# BaseNode.net
KiCad netlist of a schematic drawn in Altium Designer
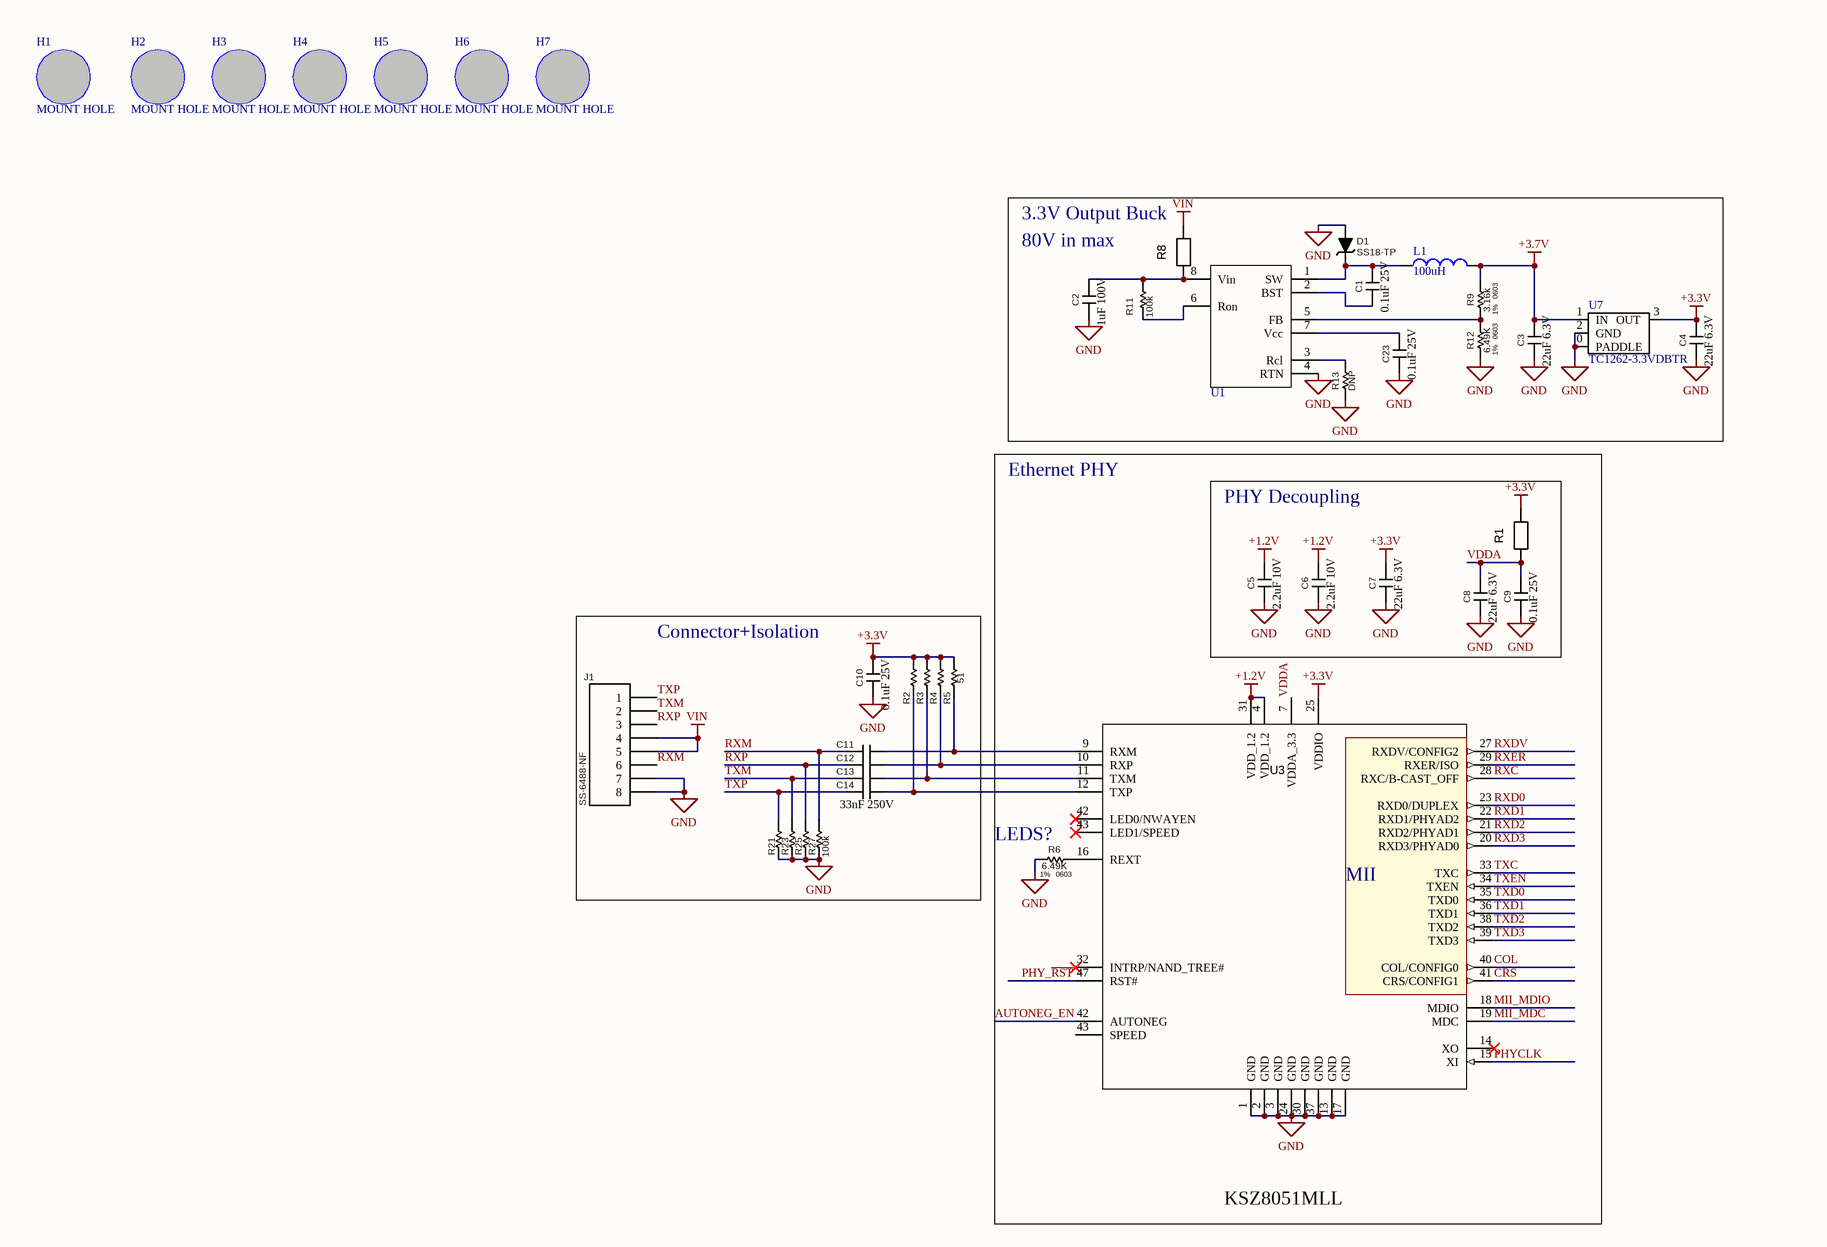
[diagram p0: BaseNode.SchDoc, top left]
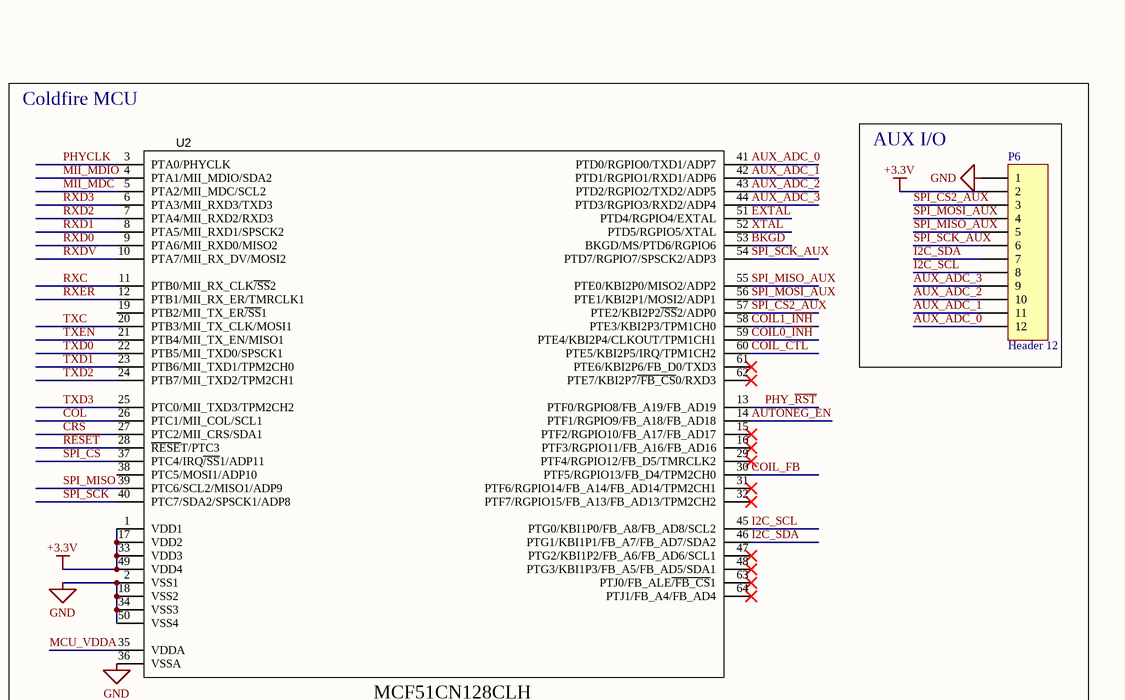
[diagram p1: BaseNode.SchDoc, top right]
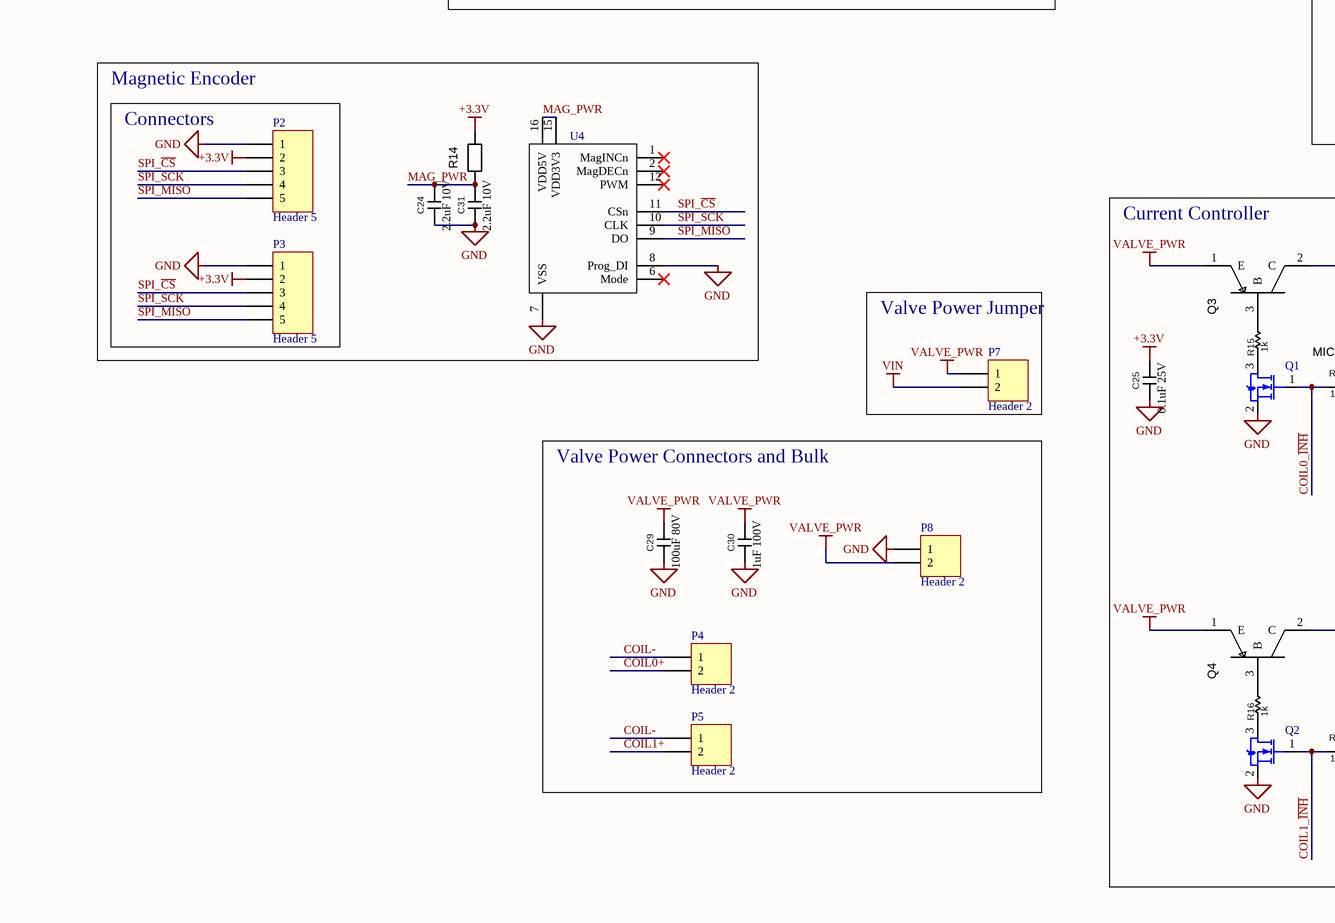
[diagram p2: BaseNode.SchDoc, bottom left]
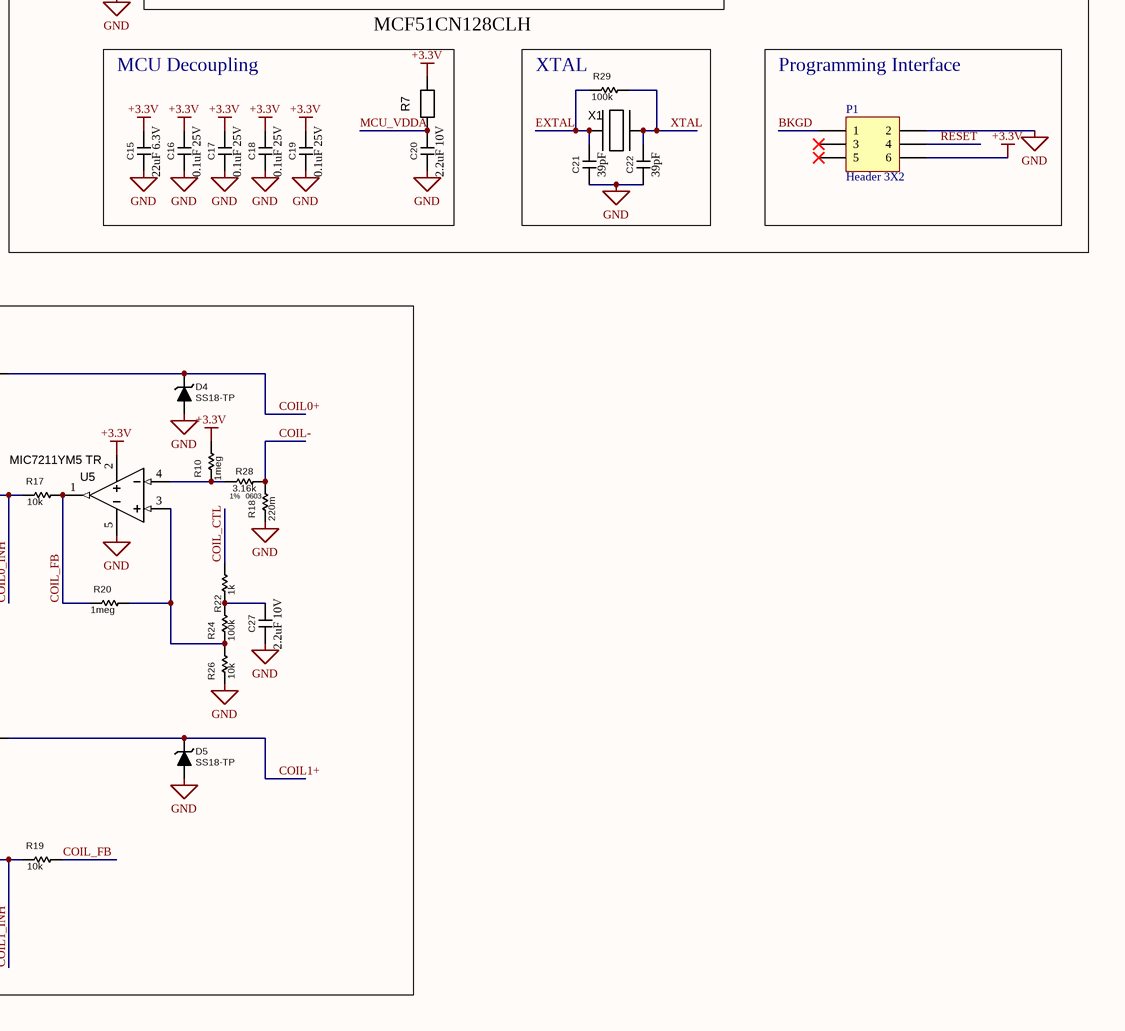
[diagram p3: BaseNode.SchDoc, bottom right]

(export (version "E")
  (design (tool "Eeschema 10.0.6"))
  (components
    (comp (ref "C1")
      (value "0.1uF 25V")
      (footprint "whong:0603")
      (description "Capacitor")
      (fields (field (name "MANUFACTURER") "Murata Electronics North America"))
      (libsource (lib "whong") (part "Capacitor"))
    )
    (comp (ref "C2")
      (value "1uF 100V")
      (footprint "whong:0805")
      (description "Capacitor")
      (fields (field (name "MANUFACTURER") "TDK Corporation"))
      (libsource (lib "whong") (part "Capacitor"))
    )
    (comp (ref "C3")
      (value "22uF 6.3V")
      (footprint "whong:1206")
      (description "Capacitor")
      (fields (field (name "MANUFACTURER") "Taiyo Yuden"))
      (libsource (lib "whong") (part "Capacitor"))
    )
    (comp (ref "C4")
      (value "22uF 6.3V")
      (footprint "whong:1206")
      (description "Capacitor")
      (fields (field (name "MANUFACTURER") "Taiyo Yuden"))
      (libsource (lib "whong") (part "Capacitor"))
    )
    (comp (ref "C5")
      (value "2.2uF 10V")
      (footprint "whong:0603")
      (description "Capacitor")
      (fields (field (name "MANUFACTURER") "Taiyo Yuden"))
      (libsource (lib "whong") (part "Capacitor"))
    )
    (comp (ref "C6")
      (value "2.2uF 10V")
      (footprint "whong:0603")
      (description "Capacitor")
      (fields (field (name "MANUFACTURER") "Taiyo Yuden"))
      (libsource (lib "whong") (part "Capacitor"))
    )
    (comp (ref "C7")
      (value "22uF 6.3V")
      (footprint "whong:1206")
      (description "Capacitor")
      (fields (field (name "MANUFACTURER") "Taiyo Yuden"))
      (libsource (lib "whong") (part "Capacitor"))
    )
    (comp (ref "C8")
      (value "22uF 6.3V")
      (footprint "whong:1206")
      (description "Capacitor")
      (fields (field (name "MANUFACTURER") "Taiyo Yuden"))
      (libsource (lib "whong") (part "Capacitor"))
    )
    (comp (ref "C9")
      (value "0.1uF 25V")
      (footprint "whong:0603")
      (description "Capacitor")
      (fields (field (name "MANUFACTURER") "Murata Electronics North America"))
      (libsource (lib "whong") (part "Capacitor"))
    )
    (comp (ref "C10")
      (value "0.1uF 25V")
      (footprint "whong:0603")
      (description "Capacitor")
      (fields (field (name "MANUFACTURER") "Murata Electronics North America"))
      (libsource (lib "whong") (part "Capacitor"))
    )
    (comp (ref "C11")
      (value "33nF 250V")
      (footprint "whong:0805")
      (description "Capacitor")
      (fields (field (name "MANUFACTURER") "TDK Corporation"))
      (libsource (lib "whong") (part "Capacitor"))
    )
    (comp (ref "C12")
      (value "33nF 250V")
      (footprint "whong:0805")
      (description "Capacitor")
      (fields (field (name "MANUFACTURER") "TDK Corporation"))
      (libsource (lib "whong") (part "Capacitor"))
    )
    (comp (ref "C13")
      (value "33nF 250V")
      (footprint "whong:0805")
      (description "Capacitor")
      (fields (field (name "MANUFACTURER") "TDK Corporation"))
      (libsource (lib "whong") (part "Capacitor"))
    )
    (comp (ref "C14")
      (value "33nF 250V")
      (footprint "whong:0805")
      (description "Capacitor")
      (fields (field (name "MANUFACTURER") "TDK Corporation"))
      (libsource (lib "whong") (part "Capacitor"))
    )
    (comp (ref "C15")
      (value "22uF 6.3V")
      (footprint "whong:1206")
      (description "Capacitor")
      (fields (field (name "MANUFACTURER") "Taiyo Yuden"))
      (libsource (lib "whong") (part "Capacitor"))
    )
    (comp (ref "C16")
      (value "0.1uF 25V")
      (footprint "whong:0603")
      (description "Capacitor")
      (fields (field (name "MANUFACTURER") "Murata Electronics North America"))
      (libsource (lib "whong") (part "Capacitor"))
    )
    (comp (ref "C17")
      (value "0.1uF 25V")
      (footprint "whong:0603")
      (description "Capacitor")
      (fields (field (name "MANUFACTURER") "Murata Electronics North America"))
      (libsource (lib "whong") (part "Capacitor"))
    )
    (comp (ref "C18")
      (value "0.1uF 25V")
      (footprint "whong:0603")
      (description "Capacitor")
      (fields (field (name "MANUFACTURER") "Murata Electronics North America"))
      (libsource (lib "whong") (part "Capacitor"))
    )
    (comp (ref "C19")
      (value "0.1uF 25V")
      (footprint "whong:0603")
      (description "Capacitor")
      (fields (field (name "MANUFACTURER") "Murata Electronics North America"))
      (libsource (lib "whong") (part "Capacitor"))
    )
    (comp (ref "C20")
      (value "2.2uF 10V")
      (footprint "whong:0603")
      (description "Capacitor")
      (fields (field (name "MANUFACTURER") "Taiyo Yuden"))
      (libsource (lib "whong") (part "Capacitor"))
    )
    (comp (ref "C21")
      (value "39pF")
      (footprint "whong:0603")
      (description "Capacitor")
      (fields (field (name "MANUFACTURER") "TDK Corporation"))
      (libsource (lib "whong") (part "Capacitor"))
    )
    (comp (ref "C22")
      (value "39pF")
      (footprint "whong:0603")
      (description "Capacitor")
      (fields (field (name "MANUFACTURER") "TDK Corporation"))
      (libsource (lib "whong") (part "Capacitor"))
    )
    (comp (ref "C23")
      (value "0.1uF 25V")
      (footprint "whong:0603")
      (description "Capacitor")
      (fields (field (name "MANUFACTURER") "Murata Electronics North America"))
      (libsource (lib "whong") (part "Capacitor"))
    )
    (comp (ref "C24")
      (value "2.2uF 10V")
      (footprint "whong:0603")
      (description "Capacitor")
      (fields (field (name "MANUFACTURER") "Taiyo Yuden"))
      (libsource (lib "whong") (part "Capacitor"))
    )
    (comp (ref "C25")
      (value "0.1uF 25V")
      (footprint "whong:0603")
      (description "Capacitor")
      (fields (field (name "MANUFACTURER") "Murata Electronics North America"))
      (libsource (lib "whong") (part "Capacitor"))
    )
    (comp (ref "C27")
      (value "2.2uF 10V")
      (footprint "whong:0603")
      (description "Capacitor")
      (fields (field (name "MANUFACTURER") "Taiyo Yuden"))
      (libsource (lib "whong") (part "Capacitor"))
    )
    (comp (ref "C29")
      (value "100uF 80V")
      (footprint "whong:Capacitor 12mm DIA POLAR")
      (description "Capacitor")
      (fields (field (name "MANUFACTURER") "Panasonic Electronic Components"))
      (libsource (lib "whong") (part "Capacitor"))
    )
    (comp (ref "C30")
      (value "1uF 100V")
      (footprint "whong:0805")
      (description "Capacitor")
      (fields (field (name "MANUFACTURER") "TDK Corporation"))
      (libsource (lib "whong") (part "Capacitor"))
    )
    (comp (ref "C31")
      (value "2.2uF 10V")
      (footprint "whong:0603")
      (description "Capacitor")
      (fields (field (name "MANUFACTURER") "Taiyo Yuden"))
      (libsource (lib "whong") (part "Capacitor"))
    )
    (comp (ref "D1")
      (value "CDBA140-G")
      (footprint "SMA-DIODE")
      (description "DIODE SCHOTTKY 40V 1A SMA")
      (fields (field (name "MANUFACTURER") "Micro Commercial Co") (field (name "MANUFACTURERPN") "SS18-TP"))
      (libsource (lib "whong") (part "CDBA140-G"))
    )
    (comp (ref "D4")
      (value "CDBA140-G")
      (footprint "SMA-DIODE")
      (description "DIODE SCHOTTKY 40V 1A SMA")
      (fields (field (name "MANUFACTURER") "Micro Commercial Co") (field (name "MANUFACTURERPN") "SS18-TP"))
      (libsource (lib "whong") (part "CDBA140-G"))
    )
    (comp (ref "D5")
      (value "CDBA140-G")
      (footprint "SMA-DIODE")
      (description "DIODE SCHOTTKY 40V 1A SMA")
      (fields (field (name "MANUFACTURER") "Micro Commercial Co") (field (name "MANUFACTURERPN") "SS18-TP"))
      (libsource (lib "whong") (part "CDBA140-G"))
    )
    (comp (ref "H1")
      (value "MOUNT HOLE")
      (footprint "MOUNT_HOLE")
      (libsource (lib "whong") (part "MOUNT HOLE"))
    )
    (comp (ref "H2")
      (value "MOUNT HOLE")
      (footprint "MOUNT_HOLE")
      (libsource (lib "whong") (part "MOUNT HOLE"))
    )
    (comp (ref "H3")
      (value "MOUNT HOLE")
      (footprint "MOUNT_HOLE")
      (libsource (lib "whong") (part "MOUNT HOLE"))
    )
    (comp (ref "H4")
      (value "MOUNT HOLE")
      (footprint "MOUNT_HOLE")
      (libsource (lib "whong") (part "MOUNT HOLE"))
    )
    (comp (ref "H5")
      (value "MOUNT HOLE")
      (footprint "MOUNT_HOLE")
      (libsource (lib "whong") (part "MOUNT HOLE"))
    )
    (comp (ref "H6")
      (value "MOUNT HOLE")
      (footprint "MOUNT_HOLE")
      (libsource (lib "whong") (part "MOUNT HOLE"))
    )
    (comp (ref "H7")
      (value "MOUNT HOLE")
      (footprint "MOUNT_HOLE")
      (libsource (lib "whong") (part "MOUNT HOLE"))
    )
    (comp (ref "J1")
      (value "SS-6488-NF")
      (footprint "whong:SS-6488-NF")
      (description "CONN 8-8 MOD JACK")
      (fields (field (name "MANUFACTURER") "Stewart Connector"))
      (libsource (lib "whong") (part "SS-6488-NF"))
    )
    (comp (ref "L1")
      (value "100uH")
      (footprint "whong:NR6028 Inductor")
      (description "Inductor")
      (fields (field (name "MANUFACTURER") "Taiyo Yuden"))
      (libsource (lib "Miscellaneous Devices") (part "Inductor"))
    )
    (comp (ref "P1")
      (value "Header 3X2")
      (footprint "HDR2X3")
      (description "Header, 3-Pin, Dual row")
      (fields (field (name "PUBLISHER") "Altium Limited"))
      (libsource (lib "Miscellaneous Connectors") (part "Header 3X2"))
    )
    (comp (ref "P2")
      (value "Header 5")
      (footprint "HDR1X5")
      (description "Header, 5-Pin")
      (fields (field (name "PUBLISHER") "Altium Limited"))
      (libsource (lib "Miscellaneous Connectors") (part "Header 5"))
    )
    (comp (ref "P3")
      (value "Header 5")
      (footprint "HDR1X5")
      (description "Header, 5-Pin")
      (fields (field (name "PUBLISHER") "Altium Limited"))
      (libsource (lib "Miscellaneous Connectors") (part "Header 5"))
    )
    (comp (ref "P4")
      (value "Header 2")
      (footprint "HDR1X2")
      (description "Header, 2-Pin")
      (fields (field (name "PUBLISHER") "Altium Limited"))
      (libsource (lib "Miscellaneous Connectors") (part "Header 2"))
    )
    (comp (ref "P5")
      (value "Header 2")
      (footprint "HDR1X2")
      (description "Header, 2-Pin")
      (fields (field (name "PUBLISHER") "Altium Limited"))
      (libsource (lib "Miscellaneous Connectors") (part "Header 2"))
    )
    (comp (ref "P6")
      (value "Header 12")
      (footprint "HDR1X12")
      (description "Header, 12-Pin")
      (fields (field (name "PUBLISHER") "Altium Limited"))
      (libsource (lib "Miscellaneous Connectors") (part "Header 12"))
    )
    (comp (ref "P7")
      (value "Header 2")
      (footprint "HDR1X2")
      (description "Header, 2-Pin")
      (fields (field (name "PUBLISHER") "Altium Limited"))
      (libsource (lib "Miscellaneous Connectors") (part "Header 2"))
    )
    (comp (ref "P8")
      (value "Header 2")
      (footprint "HDR1X2")
      (description "Header, 2-Pin")
      (fields (field (name "PUBLISHER") "Altium Limited"))
      (libsource (lib "Miscellaneous Connectors") (part "Header 2"))
    )
    (comp (ref "Q1")
      (value "NFET")
      (footprint "whong:SOT-23")
      (description "FET N-CH 100V 170MA SOT-23")
      (fields (field (name "MANUFACTURER") "Fairchild Semiconductor"))
      (libsource (lib "whong") (part "BSS123"))
    )
    (comp (ref "Q2")
      (value "NFET")
      (footprint "whong:SOT-23")
      (description "FET N-CH 100V 170MA SOT-23")
      (fields (field (name "MANUFACTURER") "Fairchild Semiconductor"))
      (libsource (lib "whong") (part "BSS123"))
    )
    (comp (ref "Q3")
      (value "~")
      (footprint "whong:SOT-89 - PBSS305PX")
      (description "TRANS PNP 80V 4A SOT89")
      (fields (field (name "MANUFACTURER") "NXP Semiconductors"))
      (libsource (lib "whong") (part "PBSS305PX,115"))
    )
    (comp (ref "Q4")
      (value "~")
      (footprint "whong:SOT-89 - PBSS305PX")
      (description "TRANS PNP 80V 4A SOT89")
      (fields (field (name "MANUFACTURER") "NXP Semiconductors"))
      (libsource (lib "whong") (part "PBSS305PX,115"))
    )
    (comp (ref "R1")
      (value "LM4041EIM3X-1.2_1")
      (footprint "whong:0603")
      (description "Ferrite")
      (fields (field (name "MANUFACTURER") "TDK Corporation"))
      (libsource (lib "whong") (part "LM4041EIM3X-1.2_1"))
    )
    (comp (ref "R2")
      (value "51")
      (footprint "whong:0603")
      (description "Resistor")
      (fields (field (name "MANUFACTURER") "Yageo") (field (name "TOLERANCE") "5%"))
      (libsource (lib "whong") (part "Resistor"))
    )
    (comp (ref "R3")
      (value "51")
      (footprint "whong:0603")
      (description "Resistor")
      (fields (field (name "MANUFACTURER") "Yageo") (field (name "TOLERANCE") "5%"))
      (libsource (lib "whong") (part "Resistor"))
    )
    (comp (ref "R4")
      (value "51")
      (footprint "whong:0603")
      (description "Resistor")
      (fields (field (name "MANUFACTURER") "Yageo") (field (name "TOLERANCE") "5%"))
      (libsource (lib "whong") (part "Resistor"))
    )
    (comp (ref "R5")
      (value "51")
      (footprint "whong:0603")
      (description "Resistor")
      (fields (field (name "MANUFACTURER") "Yageo") (field (name "TOLERANCE") "5%"))
      (libsource (lib "whong") (part "Resistor"))
    )
    (comp (ref "R6")
      (value "6.49K")
      (footprint "whong:0603")
      (description "Resistor")
      (fields
        (field (name "MANUFACTURER") "Yageo")
        (field (name "PACKAGE") "0603")
        (field (name "TOLERANCE") "1%")
      )
      (libsource (lib "JamesWhong") (part "Resistor"))
    )
    (comp (ref "R7")
      (value "LM4041EIM3X-1.2_1")
      (footprint "whong:0603")
      (description "Ferrite")
      (fields (field (name "MANUFACTURER") "TDK Corporation"))
      (libsource (lib "whong") (part "LM4041EIM3X-1.2_1"))
    )
    (comp (ref "R8")
      (value "LM4041EIM3X-1.2_1")
      (footprint "whong:0603")
      (description "Ferrite")
      (fields (field (name "MANUFACTURER") "TDK Corporation"))
      (libsource (lib "whong") (part "LM4041EIM3X-1.2_1"))
    )
    (comp (ref "R9")
      (value "3.16k")
      (footprint "whong:0603")
      (description "Resistor")
      (fields
        (field (name "MANUFACTURER") "Yageo")
        (field (name "PACKAGE") "0603")
        (field (name "TOLERANCE") "1%")
      )
      (libsource (lib "JamesWhong") (part "Resistor"))
    )
    (comp (ref "R10")
      (value "1meg")
      (footprint "whong:0603")
      (description "Resistor")
      (fields (field (name "MANUFACTURER") "Yageo") (field (name "TOLERANCE") "5%"))
      (libsource (lib "whong") (part "Resistor"))
    )
    (comp (ref "R11")
      (value "100k")
      (footprint "whong:0603")
      (description "Resistor")
      (fields (field (name "MANUFACTURER") "Yageo"))
      (libsource (lib "whong") (part "Resistor"))
    )
    (comp (ref "R12")
      (value "6.49K")
      (footprint "whong:0603")
      (description "Resistor")
      (fields
        (field (name "MANUFACTURER") "Yageo")
        (field (name "PACKAGE") "0603")
        (field (name "TOLERANCE") "1%")
      )
      (libsource (lib "JamesWhong") (part "Resistor"))
    )
    (comp (ref "R13")
      (value "DNP")
      (footprint "whong:0603")
      (description "Resistor")
      (fields (field (name "TOLERANCE") "1%"))
      (libsource (lib "JamesWhong") (part "Resistor"))
    )
    (comp (ref "R14")
      (value "LM4041EIM3X-1.2_1")
      (footprint "whong:0603")
      (description "Ferrite")
      (fields (field (name "MANUFACTURER") "TDK Corporation"))
      (libsource (lib "whong") (part "LM4041EIM3X-1.2_1"))
    )
    (comp (ref "R15")
      (value "1k")
      (footprint "whong:0603")
      (description "Resistor")
      (fields (field (name "MANUFACTURER") "Yageo") (field (name "TOLERANCE") "5%"))
      (libsource (lib "whong") (part "Resistor"))
    )
    (comp (ref "R16")
      (value "1k")
      (footprint "whong:0603")
      (description "Resistor")
      (fields (field (name "MANUFACTURER") "Yageo") (field (name "TOLERANCE") "5%"))
      (libsource (lib "whong") (part "Resistor"))
    )
    (comp (ref "R17")
      (value "10k")
      (footprint "whong:0603")
      (description "Resistor")
      (fields (field (name "MANUFACTURER") "Yageo"))
      (libsource (lib "whong") (part "Resistor"))
    )
    (comp (ref "R18")
      (value "220m")
      (footprint "whong:0805")
      (description "Resistor")
      (fields (field (name "MANUFACTURER") "Susumu"))
      (libsource (lib "whong") (part "Resistor"))
    )
    (comp (ref "R19")
      (value "10k")
      (footprint "whong:0603")
      (description "Resistor")
      (fields (field (name "MANUFACTURER") "Yageo"))
      (libsource (lib "whong") (part "Resistor"))
    )
    (comp (ref "R20")
      (value "1meg")
      (footprint "whong:0603")
      (description "Resistor")
      (fields (field (name "MANUFACTURER") "Yageo") (field (name "TOLERANCE") "5%"))
      (libsource (lib "whong") (part "Resistor"))
    )
    (comp (ref "R21")
      (value "100k")
      (footprint "whong:0603")
      (description "Resistor")
      (fields (field (name "MANUFACTURER") "Yageo"))
      (libsource (lib "whong") (part "Resistor"))
    )
    (comp (ref "R22")
      (value "1k")
      (footprint "whong:0603")
      (description "Resistor")
      (fields (field (name "MANUFACTURER") "Yageo") (field (name "TOLERANCE") "5%"))
      (libsource (lib "whong") (part "Resistor"))
    )
    (comp (ref "R23")
      (value "100k")
      (footprint "whong:0603")
      (description "Resistor")
      (fields (field (name "MANUFACTURER") "Yageo"))
      (libsource (lib "whong") (part "Resistor"))
    )
    (comp (ref "R24")
      (value "100k")
      (footprint "whong:0603")
      (description "Resistor")
      (fields (field (name "MANUFACTURER") "Yageo"))
      (libsource (lib "whong") (part "Resistor"))
    )
    (comp (ref "R25")
      (value "100k")
      (footprint "whong:0603")
      (description "Resistor")
      (fields (field (name "MANUFACTURER") "Yageo"))
      (libsource (lib "whong") (part "Resistor"))
    )
    (comp (ref "R26")
      (value "10k")
      (footprint "whong:0603")
      (description "Resistor")
      (fields (field (name "MANUFACTURER") "Yageo"))
      (libsource (lib "whong") (part "Resistor"))
    )
    (comp (ref "R27")
      (value "100k")
      (footprint "whong:0603")
      (description "Resistor")
      (fields (field (name "MANUFACTURER") "Yageo"))
      (libsource (lib "whong") (part "Resistor"))
    )
    (comp (ref "R28")
      (value "3.16k")
      (footprint "whong:0603")
      (description "Resistor")
      (fields
        (field (name "MANUFACTURER") "Yageo")
        (field (name "PACKAGE") "0603")
        (field (name "TOLERANCE") "1%")
      )
      (libsource (lib "JamesWhong") (part "Resistor"))
    )
    (comp (ref "R29")
      (value "100k")
      (footprint "whong:0603")
      (description "Resistor")
      (fields (field (name "MANUFACTURER") "Yageo"))
      (libsource (lib "whong") (part "Resistor"))
    )
    (comp (ref "U1")
      (value "LM5007MM/NOPB")
      (footprint "whong:MSOP-8")
      (description "BUCK ADJ .5A 8MSOP")
      (fields (field (name "MANUFACTURER") "National Semiconductor"))
      (libsource (lib "whong") (part "LM5007MM/NOPB"))
    )
    (comp (ref "U2")
      (value "MCF51CN128CLH")
      (footprint "LQFP-64 10x10mm .5mm pitch")
      (description "MCU Coldfire w/ Ethernet")
      (fields (field (name "MANUFACTURER") "Freescale Semiconductor"))
      (libsource (lib "whong") (part "MCF51CN128CLH"))
    )
    (comp (ref "U3")
      (value "KSZ8051MLL")
      (footprint "LQFP-48 7x7mm 0.5mm pitch")
      (description "Ethernet PHY MII")
      (fields (field (name "MANUFACTURER") "Micrel Inc"))
      (libsource (lib "whong") (part "KSZ8051MLL"))
    )
    (comp (ref "U4")
      (value "AS5045-ASSU")
      (footprint "whong:SSOP-16")
      (description "IC ENCODER PROG 12-BIT 16-SSOP")
      (fields (field (name "MANUFACTURER") "AMS"))
      (libsource (lib "whong") (part "AS5045-ASSU"))
    )
    (comp (ref "U5")
      (value "MIC7211YM5 TR")
      (footprint "whong:SOT-23-5")
      (description "IC COMPARATOR R-R SOT-23-5")
      (fields (field (name "MANUFACTURER") "Micrel Inc"))
      (libsource (lib "whong") (part "MIC7221YM5 TR"))
    )
    (comp (ref "U7")
      (value "TC1262-3.3VDBTR")
      (footprint "bdilib:SOT-223")
      (description "Regulator IC CMOS LDO 3.3V 500MA SOT223-3")
      (fields
        (field (name "MANUFACTURER") "Microchip Technology")
        (field (name "MANUFACTURERPN") "TC1262-3.3VDBTR")
      )
      (libsource (lib "whong") (part "TC1262-3.3VDBTR"))
    )
    (comp (ref "X1")
      (value "ECS-250-20-3X-EN-TR")
      (footprint "CSM-3X")
      (description "CRYSTAL 25.00000 MHZ 20PF SMD")
      (fields (field (name "MANUFACTURER") "ECS Inc"))
      (libsource (lib "whong") (part "ECS-250-20-3X-EN-TR"))
    )
  )
  (nets
    (net (code "1") (name "+1.2V") (class "Default")
      (node (ref "C5") (pin "2") (pinfunction "2_2") (pintype "passive"))
      (node (ref "C6") (pin "2") (pinfunction "2_2") (pintype "passive"))
      (node (ref "U3") (pin "31") (pinfunction "VDD_1.2_31") (pintype "passive"))
      (node (ref "U3") (pin "4") (pinfunction "VDD_1.2_4") (pintype "passive"))
    )
    (net (code "2") (name "+3.3V") (class "Default")
      (node (ref "C10") (pin "2") (pinfunction "2_2") (pintype "passive"))
      (node (ref "C15") (pin "2") (pinfunction "2_2") (pintype "passive"))
      (node (ref "C16") (pin "2") (pinfunction "2_2") (pintype "passive"))
      (node (ref "C17") (pin "2") (pinfunction "2_2") (pintype "passive"))
      (node (ref "C18") (pin "2") (pinfunction "2_2") (pintype "passive"))
      (node (ref "C19") (pin "2") (pinfunction "2_2") (pintype "passive"))
      (node (ref "C25") (pin "2") (pinfunction "2_2") (pintype "passive"))
      (node (ref "C4") (pin "2") (pinfunction "2_2") (pintype "passive"))
      (node (ref "C7") (pin "2") (pinfunction "2_2") (pintype "passive"))
      (node (ref "P1") (pin "6") (pinfunction "6_6") (pintype "passive"))
      (node (ref "P2") (pin "2") (pinfunction "2_2") (pintype "passive"))
      (node (ref "P3") (pin "2") (pinfunction "2_2") (pintype "passive"))
      (node (ref "P6") (pin "2") (pinfunction "2_2") (pintype "passive"))
      (node (ref "R1") (pin "1") (pinfunction "K_1") (pintype "passive"))
      (node (ref "R10") (pin "2") (pinfunction "2_2") (pintype "passive"))
      (node (ref "R14") (pin "1") (pinfunction "K_1") (pintype "passive"))
      (node (ref "R2") (pin "2") (pinfunction "2_2") (pintype "passive"))
      (node (ref "R3") (pin "2") (pinfunction "2_2") (pintype "passive"))
      (node (ref "R4") (pin "2") (pinfunction "2_2") (pintype "passive"))
      (node (ref "R5") (pin "2") (pinfunction "2_2") (pintype "passive"))
      (node (ref "R7") (pin "1") (pinfunction "K_1") (pintype "passive"))
      (node (ref "U2") (pin "1") (pinfunction "VDD1_1") (pintype "passive"))
      (node (ref "U2") (pin "17") (pinfunction "VDD2_17") (pintype "passive"))
      (node (ref "U2") (pin "33") (pinfunction "VDD3_33") (pintype "passive"))
      (node (ref "U2") (pin "49") (pinfunction "VDD4_49") (pintype "passive"))
      (node (ref "U3") (pin "25") (pinfunction "VDDIO_25") (pintype "passive"))
      (node (ref "U5") (pin "2") (pinfunction "V+_2") (pintype "power_in"))
      (node (ref "U7") (pin "3") (pinfunction "OUT_3") (pintype "passive"))
    )
    (net (code "3") (name "+3.7V") (class "Default")
      (node (ref "C3") (pin "2") (pinfunction "2_2") (pintype "passive"))
      (node (ref "L1") (pin "2") (pinfunction "2_2") (pintype "passive"))
      (node (ref "R9") (pin "2") (pinfunction "2_2") (pintype "passive"))
      (node (ref "U7") (pin "1") (pinfunction "IN_1") (pintype "passive"))
    )
    (net (code "4") (name "/AUTONEG_EN") (class "Default")
      (node (ref "U2") (pin "14") (pinfunction "PTF1/RGPIO9/FB_A18/FB_AD18_14") (pintype "passive"))
      (node (ref "U3") (pin "42") (pinfunction "AUTONEG_42") (pintype "passive"))
    )
    (net (code "5") (name "/AUX_ADC_0") (class "Default")
      (node (ref "P6") (pin "12") (pinfunction "12_12") (pintype "passive"))
      (node (ref "U2") (pin "41") (pinfunction "PTD0/RGPIO0/TXD1/ADP7_41") (pintype "passive"))
    )
    (net (code "6") (name "/AUX_ADC_1") (class "Default")
      (node (ref "P6") (pin "11") (pinfunction "11_11") (pintype "passive"))
      (node (ref "U2") (pin "42") (pinfunction "PTD1/RGPIO1/RXD1/ADP6_42") (pintype "passive"))
    )
    (net (code "7") (name "/AUX_ADC_2") (class "Default")
      (node (ref "P6") (pin "10") (pinfunction "10_10") (pintype "passive"))
      (node (ref "U2") (pin "43") (pinfunction "PTD2/RGPIO2/TXD2/ADP5_43") (pintype "passive"))
    )
    (net (code "8") (name "/AUX_ADC_3") (class "Default")
      (node (ref "P6") (pin "9") (pinfunction "9_9") (pintype "passive"))
      (node (ref "U2") (pin "44") (pinfunction "PTD3/RGPIO3/RXD2/ADP4_44") (pintype "passive"))
    )
    (net (code "9") (name "/BKGD") (class "Default")
      (node (ref "P1") (pin "1") (pinfunction "1_1") (pintype "passive"))
      (node (ref "U2") (pin "53") (pinfunction "BKGD/MS/PTD6/RGPIO6_53") (pintype "passive"))
    )
    (net (code "10") (name "/COIL-") (class "Default")
      (node (ref "P4") (pin "1") (pinfunction "1_1") (pintype "passive"))
      (node (ref "P5") (pin "1") (pinfunction "1_1") (pintype "passive"))
      (node (ref "R18") (pin "2") (pinfunction "2_2") (pintype "passive"))
      (node (ref "R28") (pin "2") (pinfunction "2_2") (pintype "passive"))
    )
    (net (code "11") (name "/COIL0+") (class "Default")
      (node (ref "D4") (pin "K") (pinfunction "K_K") (pintype "passive"))
      (node (ref "P4") (pin "2") (pinfunction "2_2") (pintype "passive"))
      (node (ref "Q3") (pin "2") (pinfunction "C_2") (pintype "passive"))
    )
    (net (code "12") (name "/COIL0_~{INH}") (class "Default")
      (node (ref "Q1") (pin "1") (pinfunction "G_1") (pintype "passive"))
      (node (ref "R17") (pin "1") (pinfunction "1_1") (pintype "passive"))
      (node (ref "U2") (pin "59") (pinfunction "PTE4/KBI2P4/CLKOUT/TPM1CH1_59") (pintype "passive"))
    )
    (net (code "13") (name "/COIL1+") (class "Default")
      (node (ref "D5") (pin "K") (pinfunction "K_K") (pintype "passive"))
      (node (ref "P5") (pin "2") (pinfunction "2_2") (pintype "passive"))
      (node (ref "Q4") (pin "2") (pinfunction "C_2") (pintype "passive"))
    )
    (net (code "14") (name "/COIL1_~{INH}") (class "Default")
      (node (ref "Q2") (pin "1") (pinfunction "G_1") (pintype "passive"))
      (node (ref "R19") (pin "1") (pinfunction "1_1") (pintype "passive"))
      (node (ref "U2") (pin "58") (pinfunction "PTE3/KBI2P3/TPM1CH0_58") (pintype "passive"))
    )
    (net (code "15") (name "/COIL_CTL") (class "Default")
      (node (ref "R22") (pin "2") (pinfunction "2_2") (pintype "passive"))
      (node (ref "U2") (pin "60") (pinfunction "PTE5/KBI2P5/IRQ/TPM1CH2_60") (pintype "passive"))
    )
    (net (code "16") (name "/COIL_FB") (class "Default")
      (node (ref "R17") (pin "2") (pinfunction "2_2") (pintype "passive"))
      (node (ref "R19") (pin "2") (pinfunction "2_2") (pintype "passive"))
      (node (ref "R20") (pin "1") (pinfunction "1_1") (pintype "passive"))
      (node (ref "U2") (pin "30") (pinfunction "PTF5/RGPIO13/FB_D4/TPM2CH0_30") (pintype "passive"))
      (node (ref "U5") (pin "1") (pinfunction "Out_A_1") (pintype "output"))
    )
    (net (code "17") (name "/COL") (class "Default")
      (node (ref "U2") (pin "26") (pinfunction "PTC1/MII_COL/SCL1_26") (pintype "passive"))
      (node (ref "U3") (pin "40") (pinfunction "COL/CONFIG0_40") (pintype "output"))
    )
    (net (code "18") (name "/CRS") (class "Default")
      (node (ref "U2") (pin "27") (pinfunction "PTC2/MII_CRS/SDA1_27") (pintype "passive"))
      (node (ref "U3") (pin "41") (pinfunction "CRS/CONFIG1_41") (pintype "output"))
    )
    (net (code "19") (name "/EXTAL") (class "Default")
      (node (ref "C21") (pin "2") (pinfunction "2_2") (pintype "passive"))
      (node (ref "R29") (pin "1") (pinfunction "1_1") (pintype "passive"))
      (node (ref "U2") (pin "51") (pinfunction "PTD4/RGPIO4/EXTAL_51") (pintype "passive"))
      (node (ref "X1") (pin "2") (pinfunction "A_2") (pintype "passive"))
    )
    (net (code "20") (name "/I2C_SCL") (class "Default")
      (node (ref "P6") (pin "8") (pinfunction "8_8") (pintype "passive"))
      (node (ref "U2") (pin "45") (pinfunction "PTG0/KBI1P0/FB_A8/FB_AD8/SCL2_45") (pintype "passive"))
    )
    (net (code "21") (name "/I2C_SDA") (class "Default")
      (node (ref "P6") (pin "7") (pinfunction "7_7") (pintype "passive"))
      (node (ref "U2") (pin "46") (pinfunction "PTG1/KBI1P1/FB_A7/FB_AD7/SDA2_46") (pintype "passive"))
    )
    (net (code "22") (name "/MAG_PWR") (class "Default")
      (node (ref "C24") (pin "2") (pinfunction "2_2") (pintype "passive"))
      (node (ref "C31") (pin "2") (pinfunction "2_2") (pintype "passive"))
      (node (ref "R14") (pin "2") (pinfunction "A_2") (pintype "passive"))
      (node (ref "U4") (pin "15") (pinfunction "VDD3V3_15") (pintype "passive"))
      (node (ref "U4") (pin "16") (pinfunction "VDD5V_16") (pintype "passive"))
    )
    (net (code "23") (name "/MCU_VDDA") (class "Default")
      (node (ref "C20") (pin "2") (pinfunction "2_2") (pintype "passive"))
      (node (ref "R7") (pin "2") (pinfunction "A_2") (pintype "passive"))
      (node (ref "U2") (pin "35") (pinfunction "VDDA_35") (pintype "passive"))
    )
    (net (code "24") (name "/MII_MDC") (class "Default")
      (node (ref "U2") (pin "5") (pinfunction "PTA2/MII_MDC/SCL2_5") (pintype "passive"))
      (node (ref "U3") (pin "19") (pinfunction "MDC_19") (pintype "passive"))
    )
    (net (code "25") (name "/MII_MDIO") (class "Default")
      (node (ref "U2") (pin "4") (pinfunction "PTA1/MII_MDIO/SDA2_4") (pintype "passive"))
      (node (ref "U3") (pin "18") (pinfunction "MDIO_18") (pintype "passive"))
    )
    (net (code "26") (name "/PHYCLK") (class "Default")
      (node (ref "U2") (pin "3") (pinfunction "PTA0/PHYCLK_3") (pintype "passive"))
      (node (ref "U3") (pin "15") (pinfunction "XI_15") (pintype "input"))
    )
    (net (code "27") (name "/PHY_~{RST}") (class "Default")
      (node (ref "U2") (pin "13") (pinfunction "PTF0/RGPIO8/FB_A19/FB_AD19_13") (pintype "passive"))
      (node (ref "U3") (pin "47") (pinfunction "RST#_47") (pintype "passive"))
    )
    (net (code "28") (name "/RXC") (class "Default")
      (node (ref "U2") (pin "11") (pinfunction "PTB0/MII_RX_CLK~{/SS}2_11") (pintype "passive"))
      (node (ref "U3") (pin "28") (pinfunction "RXC/B-CAST_OFF_28") (pintype "output"))
    )
    (net (code "29") (name "/RXD0") (class "Default")
      (node (ref "U2") (pin "9") (pinfunction "PTA6/MII_RXD0/MISO2_9") (pintype "passive"))
      (node (ref "U3") (pin "23") (pinfunction "RXD0/DUPLEX_23") (pintype "output"))
    )
    (net (code "30") (name "/RXD1") (class "Default")
      (node (ref "U2") (pin "8") (pinfunction "PTA5/MII_RXD1/SPSCK2_8") (pintype "passive"))
      (node (ref "U3") (pin "22") (pinfunction "RXD1/PHYAD2_22") (pintype "output"))
    )
    (net (code "31") (name "/RXD2") (class "Default")
      (node (ref "U2") (pin "7") (pinfunction "PTA4/MII_RXD2/RXD3_7") (pintype "passive"))
      (node (ref "U3") (pin "21") (pinfunction "RXD2/PHYAD1_21") (pintype "output"))
    )
    (net (code "32") (name "/RXD3") (class "Default")
      (node (ref "U2") (pin "6") (pinfunction "PTA3/MII_RXD3/TXD3_6") (pintype "passive"))
      (node (ref "U3") (pin "20") (pinfunction "RXD3/PHYAD0_20") (pintype "output"))
    )
    (net (code "33") (name "/RXDV") (class "Default")
      (node (ref "U2") (pin "10") (pinfunction "PTA7/MII_RX_DV/MOSI2_10") (pintype "passive"))
      (node (ref "U3") (pin "27") (pinfunction "RXDV/CONFIG2_27") (pintype "output"))
    )
    (net (code "34") (name "/RXER") (class "Default")
      (node (ref "U2") (pin "12") (pinfunction "PTB1/MII_RX_ER/TMRCLK1_12") (pintype "passive"))
      (node (ref "U3") (pin "29") (pinfunction "RXER/ISO_29") (pintype "output"))
    )
    (net (code "35") (name "/RXM") (class "Default")
      (node (ref "C11") (pin "1") (pinfunction "1_1") (pintype "passive"))
      (node (ref "J1") (pin "6") (pinfunction "6_6") (pintype "passive"))
      (node (ref "R27") (pin "2") (pinfunction "2_2") (pintype "passive"))
    )
    (net (code "36") (name "/RXP") (class "Default")
      (node (ref "C12") (pin "1") (pinfunction "1_1") (pintype "passive"))
      (node (ref "J1") (pin "3") (pinfunction "3_3") (pintype "passive"))
      (node (ref "R25") (pin "2") (pinfunction "2_2") (pintype "passive"))
    )
    (net (code "37") (name "/SPI_MISO") (class "Default")
      (node (ref "P2") (pin "5") (pinfunction "5_5") (pintype "passive"))
      (node (ref "P3") (pin "5") (pinfunction "5_5") (pintype "passive"))
      (node (ref "U2") (pin "39") (pinfunction "PTC6/SCL2/MISO1/ADP9_39") (pintype "passive"))
      (node (ref "U4") (pin "9") (pinfunction "DO_9") (pintype "passive"))
    )
    (net (code "38") (name "/SPI_MISO_AUX") (class "Default")
      (node (ref "P6") (pin "5") (pinfunction "5_5") (pintype "passive"))
      (node (ref "U2") (pin "55") (pinfunction "PTE0/KBI2P0/MISO2/ADP2_55") (pintype "passive"))
    )
    (net (code "39") (name "/SPI_MOSI_AUX") (class "Default")
      (node (ref "P6") (pin "4") (pinfunction "4_4") (pintype "passive"))
      (node (ref "U2") (pin "56") (pinfunction "PTE1/KBI2P1/MOSI2/ADP1_56") (pintype "passive"))
    )
    (net (code "40") (name "/SPI_SCK") (class "Default")
      (node (ref "P2") (pin "4") (pinfunction "4_4") (pintype "passive"))
      (node (ref "P3") (pin "4") (pinfunction "4_4") (pintype "passive"))
      (node (ref "U2") (pin "40") (pinfunction "PTC7/SDA2/SPSCK1/ADP8_40") (pintype "passive"))
      (node (ref "U4") (pin "10") (pinfunction "CLK_10") (pintype "passive"))
    )
    (net (code "41") (name "/SPI_SCK_AUX") (class "Default")
      (node (ref "P6") (pin "6") (pinfunction "6_6") (pintype "passive"))
      (node (ref "U2") (pin "54") (pinfunction "PTD7/RGPIO7/SPSCK2/ADP3_54") (pintype "passive"))
    )
    (net (code "42") (name "/SPI_~{CS2}_AUX") (class "Default")
      (node (ref "P6") (pin "3") (pinfunction "3_3") (pintype "passive"))
      (node (ref "U2") (pin "57") (pinfunction "PTE2/KBI2P2~{/SS}2/ADP0_57") (pintype "passive"))
    )
    (net (code "43") (name "/SPI_~{CS}") (class "Default")
      (node (ref "P2") (pin "3") (pinfunction "3_3") (pintype "passive"))
      (node (ref "P3") (pin "3") (pinfunction "3_3") (pintype "passive"))
      (node (ref "U2") (pin "37") (pinfunction "PTC4/IRQ~{/SS}1/ADP11_37") (pintype "passive"))
      (node (ref "U4") (pin "11") (pinfunction "CSn_11") (pintype "passive"))
    )
    (net (code "44") (name "/TXC") (class "Default")
      (node (ref "U2") (pin "20") (pinfunction "PTB3/MII_TX_CLK/MOSI1_20") (pintype "passive"))
      (node (ref "U3") (pin "33") (pinfunction "TXC_33") (pintype "output"))
    )
    (net (code "45") (name "/TXD0") (class "Default")
      (node (ref "U2") (pin "22") (pinfunction "PTB5/MII_TXD0/SPSCK1_22") (pintype "passive"))
      (node (ref "U3") (pin "35") (pinfunction "TXD0_35") (pintype "input"))
    )
    (net (code "46") (name "/TXD1") (class "Default")
      (node (ref "U2") (pin "23") (pinfunction "PTB6/MII_TXD1/TPM2CH0_23") (pintype "passive"))
      (node (ref "U3") (pin "36") (pinfunction "TXD1_36") (pintype "input"))
    )
    (net (code "47") (name "/TXD2") (class "Default")
      (node (ref "U2") (pin "24") (pinfunction "PTB7/MII_TXD2/TPM2CH1_24") (pintype "passive"))
      (node (ref "U3") (pin "38") (pinfunction "TXD2_38") (pintype "input"))
    )
    (net (code "48") (name "/TXD3") (class "Default")
      (node (ref "U2") (pin "25") (pinfunction "PTC0/MII_TXD3/TPM2CH2_25") (pintype "passive"))
      (node (ref "U3") (pin "39") (pinfunction "TXD3_39") (pintype "input"))
    )
    (net (code "49") (name "/TXEN") (class "Default")
      (node (ref "U2") (pin "21") (pinfunction "PTB4/MII_TX_EN/MISO1_21") (pintype "passive"))
      (node (ref "U3") (pin "34") (pinfunction "TXEN_34") (pintype "input"))
    )
    (net (code "50") (name "/TXM") (class "Default")
      (node (ref "C13") (pin "1") (pinfunction "1_1") (pintype "passive"))
      (node (ref "J1") (pin "2") (pinfunction "2_2") (pintype "passive"))
      (node (ref "R23") (pin "2") (pinfunction "2_2") (pintype "passive"))
    )
    (net (code "51") (name "/TXP") (class "Default")
      (node (ref "C14") (pin "1") (pinfunction "1_1") (pintype "passive"))
      (node (ref "J1") (pin "1") (pinfunction "1_1") (pintype "passive"))
      (node (ref "R21") (pin "2") (pinfunction "2_2") (pintype "passive"))
    )
    (net (code "52") (name "/VDDA") (class "Default")
      (node (ref "C8") (pin "2") (pinfunction "2_2") (pintype "passive"))
      (node (ref "C9") (pin "2") (pinfunction "2_2") (pintype "passive"))
      (node (ref "R1") (pin "2") (pinfunction "A_2") (pintype "passive"))
      (node (ref "U3") (pin "7") (pinfunction "VDDA_3.3_7") (pintype "passive"))
    )
    (net (code "53") (name "/XTAL") (class "Default")
      (node (ref "C22") (pin "2") (pinfunction "2_2") (pintype "passive"))
      (node (ref "R29") (pin "2") (pinfunction "2_2") (pintype "passive"))
      (node (ref "U2") (pin "52") (pinfunction "PTD5/RGPIO5/XTAL_52") (pintype "passive"))
      (node (ref "X1") (pin "1") (pinfunction "K_1") (pintype "passive"))
    )
    (net (code "54") (name "/~{RESET}") (class "Default")
      (node (ref "P1") (pin "4") (pinfunction "4_4") (pintype "passive"))
      (node (ref "U2") (pin "28") (pinfunction "~{RESE}T/PTC3_28") (pintype "passive"))
    )
    (net (code "55") (name "GND") (class "Default")
      (node (ref "C10") (pin "1") (pinfunction "1_1") (pintype "passive"))
      (node (ref "C15") (pin "1") (pinfunction "1_1") (pintype "passive"))
      (node (ref "C16") (pin "1") (pinfunction "1_1") (pintype "passive"))
      (node (ref "C17") (pin "1") (pinfunction "1_1") (pintype "passive"))
      (node (ref "C18") (pin "1") (pinfunction "1_1") (pintype "passive"))
      (node (ref "C19") (pin "1") (pinfunction "1_1") (pintype "passive"))
      (node (ref "C2") (pin "1") (pinfunction "1_1") (pintype "passive"))
      (node (ref "C20") (pin "1") (pinfunction "1_1") (pintype "passive"))
      (node (ref "C21") (pin "1") (pinfunction "1_1") (pintype "passive"))
      (node (ref "C22") (pin "1") (pinfunction "1_1") (pintype "passive"))
      (node (ref "C23") (pin "1") (pinfunction "1_1") (pintype "passive"))
      (node (ref "C24") (pin "1") (pinfunction "1_1") (pintype "passive"))
      (node (ref "C25") (pin "1") (pinfunction "1_1") (pintype "passive"))
      (node (ref "C27") (pin "1") (pinfunction "1_1") (pintype "passive"))
      (node (ref "C29") (pin "1") (pinfunction "1_1") (pintype "passive"))
      (node (ref "C3") (pin "1") (pinfunction "1_1") (pintype "passive"))
      (node (ref "C30") (pin "1") (pinfunction "1_1") (pintype "passive"))
      (node (ref "C31") (pin "1") (pinfunction "1_1") (pintype "passive"))
      (node (ref "C4") (pin "1") (pinfunction "1_1") (pintype "passive"))
      (node (ref "C5") (pin "1") (pinfunction "1_1") (pintype "passive"))
      (node (ref "C6") (pin "1") (pinfunction "1_1") (pintype "passive"))
      (node (ref "C7") (pin "1") (pinfunction "1_1") (pintype "passive"))
      (node (ref "C8") (pin "1") (pinfunction "1_1") (pintype "passive"))
      (node (ref "C9") (pin "1") (pinfunction "1_1") (pintype "passive"))
      (node (ref "D1") (pin "A") (pinfunction "A_A") (pintype "passive"))
      (node (ref "D4") (pin "A") (pinfunction "A_A") (pintype "passive"))
      (node (ref "D5") (pin "A") (pinfunction "A_A") (pintype "passive"))
      (node (ref "J1") (pin "7") (pinfunction "7_7") (pintype "passive"))
      (node (ref "J1") (pin "8") (pinfunction "8_8") (pintype "passive"))
      (node (ref "P1") (pin "2") (pinfunction "2_2") (pintype "passive"))
      (node (ref "P2") (pin "1") (pinfunction "1_1") (pintype "passive"))
      (node (ref "P3") (pin "1") (pinfunction "1_1") (pintype "passive"))
      (node (ref "P6") (pin "1") (pinfunction "1_1") (pintype "passive"))
      (node (ref "P8") (pin "1") (pinfunction "1_1") (pintype "passive"))
      (node (ref "Q1") (pin "2") (pintype "passive"))
      (node (ref "Q2") (pin "2") (pintype "passive"))
      (node (ref "R12") (pin "1") (pinfunction "1_1") (pintype "passive"))
      (node (ref "R13") (pin "1") (pinfunction "1_1") (pintype "passive"))
      (node (ref "R18") (pin "1") (pinfunction "1_1") (pintype "passive"))
      (node (ref "R21") (pin "1") (pinfunction "1_1") (pintype "passive"))
      (node (ref "R23") (pin "1") (pinfunction "1_1") (pintype "passive"))
      (node (ref "R25") (pin "1") (pinfunction "1_1") (pintype "passive"))
      (node (ref "R26") (pin "1") (pinfunction "1_1") (pintype "passive"))
      (node (ref "R27") (pin "1") (pinfunction "1_1") (pintype "passive"))
      (node (ref "R6") (pin "1") (pinfunction "1_1") (pintype "passive"))
      (node (ref "U1") (pin "4") (pinfunction "RTN_4") (pintype "passive"))
      (node (ref "U2") (pin "18") (pinfunction "VSS2_18") (pintype "passive"))
      (node (ref "U2") (pin "2") (pinfunction "VSS1_2") (pintype "passive"))
      (node (ref "U2") (pin "34") (pinfunction "VSS3_34") (pintype "passive"))
      (node (ref "U2") (pin "36") (pinfunction "VSSA_36") (pintype "passive"))
      (node (ref "U2") (pin "50") (pinfunction "VSS4_50") (pintype "passive"))
      (node (ref "U3") (pin "1") (pinfunction "GND_1") (pintype "passive"))
      (node (ref "U3") (pin "13") (pinfunction "GND_13") (pintype "passive"))
      (node (ref "U3") (pin "17") (pinfunction "GND_17") (pintype "passive"))
      (node (ref "U3") (pin "2") (pinfunction "GND_2") (pintype "passive"))
      (node (ref "U3") (pin "24") (pinfunction "GND_24") (pintype "passive"))
      (node (ref "U3") (pin "3") (pinfunction "GND_3") (pintype "passive"))
      (node (ref "U3") (pin "30") (pinfunction "GND_30") (pintype "passive"))
      (node (ref "U3") (pin "37") (pinfunction "GND_37") (pintype "passive"))
      (node (ref "U4") (pin "7") (pinfunction "VSS_7") (pintype "passive"))
      (node (ref "U4") (pin "8") (pinfunction "Prog_DI_8") (pintype "passive"))
      (node (ref "U5") (pin "5") (pinfunction "V-_5") (pintype "power_in"))
      (node (ref "U7") (pin "0") (pinfunction "PADDLE_0") (pintype "passive"))
      (node (ref "U7") (pin "2") (pinfunction "GND_2") (pintype "passive"))
    )
    (net (code "56") (name "Net-(C27-Pad2)") (class "Default")
      (node (ref "C27") (pin "2") (pinfunction "2_2") (pintype "passive"))
      (node (ref "R22") (pin "1") (pinfunction "1_1") (pintype "passive"))
      (node (ref "R24") (pin "2") (pinfunction "2_2") (pintype "passive"))
    )
    (net (code "57") (name "Net-(Q1-Pad3)") (class "Default")
      (node (ref "Q1") (pin "3") (pintype "passive"))
      (node (ref "R15") (pin "1") (pinfunction "1_1") (pintype "passive"))
    )
    (net (code "58") (name "Net-(Q2-Pad3)") (class "Default")
      (node (ref "Q2") (pin "3") (pintype "passive"))
      (node (ref "R16") (pin "1") (pinfunction "1_1") (pintype "passive"))
    )
    (net (code "59") (name "Net-(Q3-B)") (class "Default")
      (node (ref "Q3") (pin "3") (pinfunction "B_3") (pintype "passive"))
      (node (ref "R15") (pin "2") (pinfunction "2_2") (pintype "passive"))
    )
    (net (code "60") (name "Net-(Q4-B)") (class "Default")
      (node (ref "Q4") (pin "3") (pinfunction "B_3") (pintype "passive"))
      (node (ref "R16") (pin "2") (pinfunction "2_2") (pintype "passive"))
    )
    (net (code "61") (name "Net-(R8-A)") (class "Default")
      (node (ref "C2") (pin "2") (pinfunction "2_2") (pintype "passive"))
      (node (ref "R11") (pin "2") (pinfunction "2_2") (pintype "passive"))
      (node (ref "R8") (pin "2") (pinfunction "A_2") (pintype "passive"))
      (node (ref "U1") (pin "8") (pinfunction "Vin_8") (pintype "passive"))
    )
    (net (code "62") (name "Net-(U1-BST)") (class "Default")
      (node (ref "C1") (pin "1") (pinfunction "1_1") (pintype "passive"))
      (node (ref "U1") (pin "2") (pinfunction "BST_2") (pintype "passive"))
    )
    (net (code "63") (name "Net-(U1-FB)") (class "Default")
      (node (ref "R12") (pin "2") (pinfunction "2_2") (pintype "passive"))
      (node (ref "R9") (pin "1") (pinfunction "1_1") (pintype "passive"))
      (node (ref "U1") (pin "5") (pinfunction "FB_5") (pintype "passive"))
    )
    (net (code "64") (name "Net-(U1-Rcl)") (class "Default")
      (node (ref "R13") (pin "2") (pinfunction "2_2") (pintype "passive"))
      (node (ref "U1") (pin "3") (pinfunction "Rcl_3") (pintype "passive"))
    )
    (net (code "65") (name "Net-(U1-Ron)") (class "Default")
      (node (ref "R11") (pin "1") (pinfunction "1_1") (pintype "passive"))
      (node (ref "U1") (pin "6") (pinfunction "Ron_6") (pintype "passive"))
    )
    (net (code "66") (name "Net-(U1-SW)") (class "Default")
      (node (ref "C1") (pin "2") (pinfunction "2_2") (pintype "passive"))
      (node (ref "D1") (pin "K") (pinfunction "K_K") (pintype "passive"))
      (node (ref "L1") (pin "1") (pinfunction "1_1") (pintype "passive"))
      (node (ref "U1") (pin "1") (pinfunction "SW_1") (pintype "passive"))
    )
    (net (code "67") (name "Net-(U1-Vcc)") (class "Default")
      (node (ref "C23") (pin "2") (pinfunction "2_2") (pintype "passive"))
      (node (ref "U1") (pin "7") (pinfunction "Vcc_7") (pintype "passive"))
    )
    (net (code "68") (name "Net-(U3-REXT)") (class "Default")
      (node (ref "R6") (pin "2") (pinfunction "2_2") (pintype "passive"))
      (node (ref "U3") (pin "16") (pinfunction "REXT_16") (pintype "passive"))
    )
    (net (code "69") (name "Net-(U3-RXM)") (class "Default")
      (node (ref "C11") (pin "2") (pinfunction "2_2") (pintype "passive"))
      (node (ref "R5") (pin "1") (pinfunction "1_1") (pintype "passive"))
      (node (ref "U3") (pin "9") (pinfunction "RXM_9") (pintype "passive"))
    )
    (net (code "70") (name "Net-(U3-RXP)") (class "Default")
      (node (ref "C12") (pin "2") (pinfunction "2_2") (pintype "passive"))
      (node (ref "R4") (pin "1") (pinfunction "1_1") (pintype "passive"))
      (node (ref "U3") (pin "10") (pinfunction "RXP_10") (pintype "passive"))
    )
    (net (code "71") (name "Net-(U3-TXM)") (class "Default")
      (node (ref "C13") (pin "2") (pinfunction "2_2") (pintype "passive"))
      (node (ref "R3") (pin "1") (pinfunction "1_1") (pintype "passive"))
      (node (ref "U3") (pin "11") (pinfunction "TXM_11") (pintype "passive"))
    )
    (net (code "72") (name "Net-(U3-TXP)") (class "Default")
      (node (ref "C14") (pin "2") (pinfunction "2_2") (pintype "passive"))
      (node (ref "R2") (pin "1") (pinfunction "1_1") (pintype "passive"))
      (node (ref "U3") (pin "12") (pinfunction "TXP_12") (pintype "passive"))
    )
    (net (code "73") (name "Net-(U5-IN+_A)") (class "Default")
      (node (ref "R20") (pin "2") (pinfunction "2_2") (pintype "passive"))
      (node (ref "R24") (pin "1") (pinfunction "1_1") (pintype "passive"))
      (node (ref "R26") (pin "2") (pinfunction "2_2") (pintype "passive"))
      (node (ref "U5") (pin "3") (pinfunction "IN+_A_3") (pintype "input"))
    )
    (net (code "74") (name "Net-(U5-IN-_A)") (class "Default")
      (node (ref "R10") (pin "1") (pinfunction "1_1") (pintype "passive"))
      (node (ref "R28") (pin "1") (pinfunction "1_1") (pintype "passive"))
      (node (ref "U5") (pin "4") (pinfunction "IN-_A_4") (pintype "input"))
    )
    (net (code "75") (name "VALVE_PWR") (class "Default")
      (node (ref "C29") (pin "2") (pinfunction "2_2") (pintype "passive"))
      (node (ref "C30") (pin "2") (pinfunction "2_2") (pintype "passive"))
      (node (ref "P7") (pin "1") (pinfunction "1_1") (pintype "passive"))
      (node (ref "P8") (pin "2") (pinfunction "2_2") (pintype "passive"))
      (node (ref "Q3") (pin "1") (pinfunction "E_1") (pintype "passive"))
      (node (ref "Q4") (pin "1") (pinfunction "E_1") (pintype "passive"))
    )
    (net (code "76") (name "VIN") (class "Default")
      (node (ref "J1") (pin "4") (pinfunction "4_4") (pintype "passive"))
      (node (ref "J1") (pin "5") (pinfunction "5_5") (pintype "passive"))
      (node (ref "P7") (pin "2") (pinfunction "2_2") (pintype "passive"))
      (node (ref "R8") (pin "1") (pinfunction "K_1") (pintype "passive"))
    )
    (net (code "77") (name "unconnected-(P1-Pad3)") (class "Default")
      (node (ref "P1") (pin "3") (pinfunction "3_3") (pintype "passive+no_connect"))
    )
    (net (code "78") (name "unconnected-(P1-Pad5)") (class "Default")
      (node (ref "P1") (pin "5") (pinfunction "5_5") (pintype "passive+no_connect"))
    )
    (net (code "79") (name "unconnected-(U2-PTB2{slash}MII_TX_ER~{{slash}SS}1-Pad19)") (class "Default")
      (node (ref "U2") (pin "19") (pinfunction "PTB2/MII_TX_ER~{/SS}1_19") (pintype "passive"))
    )
    (net (code "80") (name "unconnected-(U2-PTC5{slash}MOSI1{slash}ADP10-Pad38)") (class "Default")
      (node (ref "U2") (pin "38") (pinfunction "PTC5/MOSI1/ADP10_38") (pintype "passive"))
    )
    (net (code "81") (name "unconnected-(U2-PTE6{slash}KBI2P6{slash}FB_D0{slash}TXD3-Pad61)") (class "Default")
      (node (ref "U2") (pin "61") (pinfunction "PTE6/KBI2P6/FB_D0/TXD3_61") (pintype "passive+no_connect"))
    )
    (net (code "82") (name "unconnected-(U2-PTE7{slash}KBI2P7~{{slash}FB_CS}0{slash}RXD3-Pad62)") (class "Default")
      (node (ref "U2") (pin "62") (pinfunction "PTE7/KBI2P7~{/FB_CS}0/RXD3_62") (pintype "passive+no_connect"))
    )
    (net (code "83") (name "unconnected-(U2-PTF2{slash}RGPIO10{slash}FB_A17{slash}FB_AD17-Pad15)") (class "Default")
      (node (ref "U2") (pin "15") (pinfunction "PTF2/RGPIO10/FB_A17/FB_AD17_15") (pintype "passive+no_connect"))
    )
    (net (code "84") (name "unconnected-(U2-PTF3{slash}RGPIO11{slash}FB_A16{slash}FB_AD16-Pad16)") (class "Default")
      (node (ref "U2") (pin "16") (pinfunction "PTF3/RGPIO11/FB_A16/FB_AD16_16") (pintype "passive+no_connect"))
    )
    (net (code "85") (name "unconnected-(U2-PTF4{slash}RGPIO12{slash}FB_D5{slash}TMRCLK2-Pad29)") (class "Default")
      (node (ref "U2") (pin "29") (pinfunction "PTF4/RGPIO12/FB_D5/TMRCLK2_29") (pintype "passive+no_connect"))
    )
    (net (code "86") (name "unconnected-(U2-PTF6{slash}RGPIO14{slash}FB_A14{slash}FB_AD14{slash}TPM2CH1-Pad31)") (class "Default")
      (node (ref "U2") (pin "31") (pinfunction "PTF6/RGPIO14/FB_A14/FB_AD14/TPM2CH1_31") (pintype "passive+no_connect"))
    )
    (net (code "87") (name "unconnected-(U2-PTF7{slash}RGPIO15{slash}FB_A13{slash}FB_AD13{slash}TPM2CH2-Pad32)") (class "Default")
      (node (ref "U2") (pin "32") (pinfunction "PTF7/RGPIO15/FB_A13/FB_AD13/TPM2CH2_32") (pintype "passive+no_connect"))
    )
    (net (code "88") (name "unconnected-(U2-PTG2{slash}KBI1P2{slash}FB_A6{slash}FB_AD6{slash}SCL1-Pad47)") (class "Default")
      (node (ref "U2") (pin "47") (pinfunction "PTG2/KBI1P2/FB_A6/FB_AD6/SCL1_47") (pintype "passive+no_connect"))
    )
    (net (code "89") (name "unconnected-(U2-PTG3{slash}KBI1P3{slash}FB_A5{slash}FB_AD5{slash}SDA1-Pad48)") (class "Default")
      (node (ref "U2") (pin "48") (pinfunction "PTG3/KBI1P3/FB_A5/FB_AD5/SDA1_48") (pintype "passive+no_connect"))
    )
    (net (code "90") (name "unconnected-(U2-PTJ0{slash}FB_ALE~{{slash}FB_CS}1-Pad63)") (class "Default")
      (node (ref "U2") (pin "63") (pinfunction "PTJ0/FB_ALE~{/FB_CS}1_63") (pintype "passive+no_connect"))
    )
    (net (code "91") (name "unconnected-(U2-PTJ1{slash}FB_A4{slash}FB_AD4-Pad64)") (class "Default")
      (node (ref "U2") (pin "64") (pinfunction "PTJ1/FB_A4/FB_AD4_64") (pintype "passive+no_connect"))
    )
    (net (code "92") (name "unconnected-(U3-INTRP{slash}NAND_TREE#-Pad32)") (class "Default")
      (node (ref "U3") (pin "32") (pinfunction "INTRP/NAND_TREE#_32") (pintype "passive+no_connect"))
    )
    (net (code "93") (name "unconnected-(U3-LED0{slash}NWAYEN-Pad42)") (class "Default")
      (node (ref "U3") (pin "42") (pinfunction "LED0/NWAYEN_42") (pintype "passive+no_connect"))
    )
    (net (code "94") (name "unconnected-(U3-LED1{slash}SPEED-Pad43)") (class "Default")
      (node (ref "U3") (pin "43") (pinfunction "LED1/SPEED_43") (pintype "passive+no_connect"))
    )
    (net (code "95") (name "unconnected-(U3-SPEED-Pad43)") (class "Default")
      (node (ref "U3") (pin "43") (pinfunction "SPEED_43") (pintype "passive"))
    )
    (net (code "96") (name "unconnected-(U3-XO-Pad14)") (class "Default")
      (node (ref "U3") (pin "14") (pinfunction "XO_14") (pintype "passive+no_connect"))
    )
    (net (code "97") (name "unconnected-(U4-MagDECn-Pad2)") (class "Default")
      (node (ref "U4") (pin "2") (pinfunction "MagDECn_2") (pintype "passive+no_connect"))
    )
    (net (code "98") (name "unconnected-(U4-MagINCn-Pad1)") (class "Default")
      (node (ref "U4") (pin "1") (pinfunction "MagINCn_1") (pintype "passive+no_connect"))
    )
    (net (code "99") (name "unconnected-(U4-Mode-Pad6)") (class "Default")
      (node (ref "U4") (pin "6") (pinfunction "Mode_6") (pintype "passive+no_connect"))
    )
    (net (code "100") (name "unconnected-(U4-PWM-Pad12)") (class "Default")
      (node (ref "U4") (pin "12") (pinfunction "PWM_12") (pintype "passive+no_connect"))
    )
  )
)
